# pot-boardD.net
KiCad netlist of a schematic drawn in EAGLE
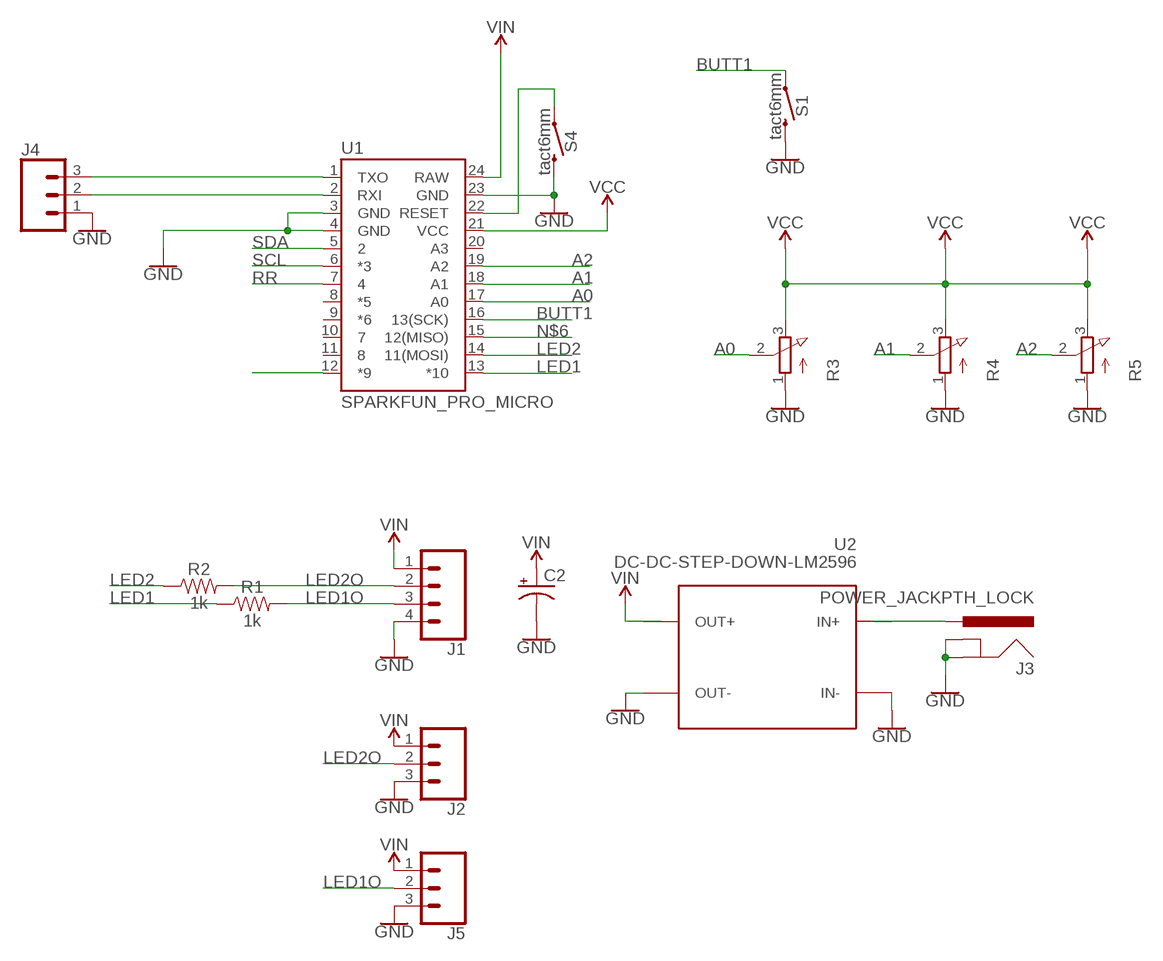
[diagram p0: schematic, sheet 1]

(export (version "E")
  (design (tool "Eeschema 10.0.6"))
  (components
    (comp (ref "C2")
      (value "CPOL-USE3.5-8")
      (footprint "eagle-import:E3,5-8")
      (libsource (lib "eagle-import") (part "CPOL-USE3.5-8"))
    )
    (comp (ref "J1")
      (value "CONN_04")
      (footprint "eagle-import:1X04")
      (libsource (lib "eagle-import") (part "CONN_04"))
    )
    (comp (ref "J2")
      (value "CONN_03")
      (footprint "eagle-import:1X03")
      (libsource (lib "eagle-import") (part "CONN_03"))
    )
    (comp (ref "J3")
      (value "POWER_JACKPTH_LOCK")
      (footprint "eagle-import:POWER_JACK_PTH_LOCK")
      (libsource (lib "eagle-import") (part "POWER_JACKPTH_LOCK"))
    )
    (comp (ref "J4")
      (value "CONN_03")
      (footprint "eagle-import:1X03")
      (libsource (lib "eagle-import") (part "CONN_03"))
    )
    (comp (ref "J5")
      (value "CONN_03")
      (footprint "eagle-import:1X03")
      (libsource (lib "eagle-import") (part "CONN_03"))
    )
    (comp (ref "R1")
      (value "1k")
      (footprint "eagle-import:AXIAL-0.3")
      (libsource (lib "eagle-import") (part "1KOHM-HORIZ-1/4W-5%"))
    )
    (comp (ref "R2")
      (value "1k")
      (footprint "eagle-import:AXIAL-0.3")
      (libsource (lib "eagle-import") (part "1KOHM-HORIZ-1/4W-5%"))
    )
    (comp (ref "R3")
      (value "3RP/1610N")
      (footprint "eagle-import:3RP_1610N")
      (libsource (lib "eagle-import") (part "3RP/1610N"))
    )
    (comp (ref "R4")
      (value "3RP/1610N")
      (footprint "eagle-import:3RP_1610N")
      (libsource (lib "eagle-import") (part "3RP/1610N"))
    )
    (comp (ref "R5")
      (value "3RP/1610N")
      (footprint "eagle-import:3RP_1610N")
      (libsource (lib "eagle-import") (part "3RP/1610N"))
    )
    (comp (ref "S1")
      (value "tact6mm")
      (footprint "eagle-import:TACTILE_SWITCH_PTH_6.0MM")
      (libsource (lib "eagle-import") (part "MOMENTARY-SWITCH-SPST-PTH-6.0MM"))
    )
    (comp (ref "S4")
      (value "tact6mm")
      (footprint "eagle-import:TACTILE_SWITCH_PTH_6.0MM")
      (libsource (lib "eagle-import") (part "MOMENTARY-SWITCH-SPST-PTH-6.0MM"))
    )
    (comp (ref "U1")
      (value "SPARKFUN_PRO_MICRO")
      (footprint "eagle-import:SPARKFUN_PRO_MICRO")
      (libsource (lib "eagle-import") (part "SPARKFUN_PRO_MICRO"))
    )
    (comp (ref "U2")
      (value "DC-DC-STEP-DOWN-LM2596")
      (footprint "eagle-import:DC-DC-STEP-DOWN-LM2596")
      (libsource (lib "eagle-import") (part "DC-DC-STEP-DOWN-LM2596"))
    )
  )
  (nets
    (net (code "1") (name "/A0") (class "Default")
      (node (ref "R3") (pin "2") (pinfunction "S_2") (pintype "passive"))
      (node (ref "U1") (pin "17") (pinfunction "A0_17") (pintype "bidirectional"))
    )
    (net (code "2") (name "/A1") (class "Default")
      (node (ref "R4") (pin "2") (pinfunction "S_2") (pintype "passive"))
      (node (ref "U1") (pin "18") (pinfunction "A1_18") (pintype "bidirectional"))
    )
    (net (code "3") (name "/A2") (class "Default")
      (node (ref "R5") (pin "2") (pinfunction "S_2") (pintype "passive"))
      (node (ref "U1") (pin "19") (pinfunction "A2_19") (pintype "bidirectional"))
    )
    (net (code "4") (name "/BUTT1") (class "Default")
      (node (ref "S1") (pin "1") (pinfunction "1_1") (pintype "passive"))
      (node (ref "U1") (pin "16") (pinfunction "13(SCK)_16") (pintype "bidirectional"))
    )
    (net (code "5") (name "/LED1") (class "Default")
      (node (ref "R1") (pin "P$1") (pinfunction "1_P$1") (pintype "passive"))
      (node (ref "U1") (pin "13") (pinfunction "*10_13") (pintype "bidirectional"))
    )
    (net (code "6") (name "/LED1O") (class "Default")
      (node (ref "J1") (pin "3") (pinfunction "3_3") (pintype "passive"))
      (node (ref "J5") (pin "2") (pinfunction "2_2") (pintype "passive"))
      (node (ref "R1") (pin "P$2") (pinfunction "2_P$2") (pintype "passive"))
    )
    (net (code "7") (name "/LED2") (class "Default")
      (node (ref "R2") (pin "P$1") (pinfunction "1_P$1") (pintype "passive"))
      (node (ref "U1") (pin "14") (pinfunction "11(MOSI)_14") (pintype "bidirectional"))
    )
    (net (code "8") (name "/LED2O") (class "Default")
      (node (ref "J1") (pin "2") (pinfunction "2_2") (pintype "passive"))
      (node (ref "J2") (pin "2") (pinfunction "2_2") (pintype "passive"))
      (node (ref "R2") (pin "P$2") (pinfunction "2_P$2") (pintype "passive"))
    )
    (net (code "9") (name "/N$6") (class "Default")
      (node (ref "U1") (pin "15") (pinfunction "12(MISO)_15") (pintype "bidirectional"))
    )
    (net (code "10") (name "/RR") (class "Default")
      (node (ref "U1") (pin "7") (pinfunction "4_7") (pintype "bidirectional"))
    )
    (net (code "11") (name "/SCL") (class "Default")
      (node (ref "U1") (pin "6") (pinfunction "*3_6") (pintype "bidirectional"))
    )
    (net (code "12") (name "/SDA") (class "Default")
      (node (ref "U1") (pin "5") (pinfunction "2_5") (pintype "bidirectional"))
    )
    (net (code "13") (name "GND") (class "Default")
      (node (ref "C2") (pin "-") (pinfunction "-_-") (pintype "passive"))
      (node (ref "J1") (pin "4") (pinfunction "4_4") (pintype "passive"))
      (node (ref "J2") (pin "3") (pinfunction "3_3") (pintype "passive"))
      (node (ref "J3") (pin "GND") (pinfunction "GND_GND") (pintype "bidirectional"))
      (node (ref "J3") (pin "GNDBREAK") (pinfunction "GNDBREAK_GNDBREAK") (pintype "bidirectional"))
      (node (ref "J4") (pin "1") (pinfunction "1_1") (pintype "passive"))
      (node (ref "J5") (pin "3") (pinfunction "3_3") (pintype "passive"))
      (node (ref "R3") (pin "1") (pinfunction "A_1") (pintype "passive"))
      (node (ref "R4") (pin "1") (pinfunction "A_1") (pintype "passive"))
      (node (ref "R5") (pin "1") (pinfunction "A_1") (pintype "passive"))
      (node (ref "S1") (pin "3") (pinfunction "2_3") (pintype "passive"))
      (node (ref "S4") (pin "3") (pinfunction "2_3") (pintype "passive"))
      (node (ref "U1") (pin "23") (pinfunction "GND_23") (pintype "power_in"))
      (node (ref "U1") (pin "3") (pinfunction "GND_3") (pintype "power_in"))
      (node (ref "U1") (pin "4") (pinfunction "GND_4") (pintype "power_in"))
      (node (ref "U2") (pin "IN-") (pinfunction "IN-_IN-") (pintype "bidirectional"))
      (node (ref "U2") (pin "OUT-") (pinfunction "OUT-_OUT-") (pintype "bidirectional"))
    )
    (net (code "14") (name "Net-(J3-PadPWR)") (class "Default")
      (node (ref "J3") (pin "PWR") (pinfunction "PWR_PWR") (pintype "bidirectional"))
      (node (ref "U2") (pin "IN+") (pinfunction "IN+_IN+") (pintype "bidirectional"))
    )
    (net (code "15") (name "Net-(U1-RESET)") (class "Default")
      (node (ref "S4") (pin "1") (pinfunction "1_1") (pintype "passive"))
      (node (ref "U1") (pin "22") (pinfunction "RESET_22") (pintype "bidirectional"))
    )
    (net (code "16") (name "Net-(U1-RXI)") (class "Default")
      (node (ref "J4") (pin "2") (pinfunction "2_2") (pintype "passive"))
      (node (ref "U1") (pin "2") (pinfunction "RXI_2") (pintype "bidirectional"))
    )
    (net (code "17") (name "Net-(U1-TXO)") (class "Default")
      (node (ref "J4") (pin "3") (pinfunction "3_3") (pintype "passive"))
      (node (ref "U1") (pin "1") (pinfunction "TXO_1") (pintype "bidirectional"))
    )
    (net (code "18") (name "VCC") (class "Default")
      (node (ref "R3") (pin "3") (pinfunction "E_3") (pintype "passive"))
      (node (ref "R4") (pin "3") (pinfunction "E_3") (pintype "passive"))
      (node (ref "R5") (pin "3") (pinfunction "E_3") (pintype "passive"))
      (node (ref "U1") (pin "21") (pinfunction "VCC_21") (pintype "power_in"))
    )
    (net (code "19") (name "VIN") (class "Default")
      (node (ref "C2") (pin "+") (pinfunction "+_+") (pintype "passive"))
      (node (ref "J1") (pin "1") (pinfunction "1_1") (pintype "passive"))
      (node (ref "J2") (pin "1") (pinfunction "1_1") (pintype "passive"))
      (node (ref "J5") (pin "1") (pinfunction "1_1") (pintype "passive"))
      (node (ref "U1") (pin "24") (pinfunction "RAW_24") (pintype "power_in"))
    )
    (net (code "20") (name "unconnected-(U1-*5-Pad8)") (class "Default")
      (node (ref "U1") (pin "8") (pinfunction "*5_8") (pintype "bidirectional"))
    )
    (net (code "21") (name "unconnected-(U1-*6-Pad9)") (class "Default")
      (node (ref "U1") (pin "9") (pinfunction "*6_9") (pintype "bidirectional"))
    )
    (net (code "22") (name "unconnected-(U1-*9-Pad12)") (class "Default")
      (node (ref "U1") (pin "12") (pinfunction "*9_12") (pintype "bidirectional"))
    )
    (net (code "23") (name "unconnected-(U1-7-Pad10)") (class "Default")
      (node (ref "U1") (pin "10") (pinfunction "7_10") (pintype "bidirectional"))
    )
    (net (code "24") (name "unconnected-(U1-8-Pad11)") (class "Default")
      (node (ref "U1") (pin "11") (pinfunction "8_11") (pintype "bidirectional"))
    )
    (net (code "25") (name "unconnected-(U1-A3-Pad20)") (class "Default")
      (node (ref "U1") (pin "20") (pinfunction "A3_20") (pintype "bidirectional"))
    )
    (net (code "26") (name "unconnected-(U2-PadOUT+)") (class "Default")
      (node (ref "U2") (pin "OUT+") (pinfunction "OUT+_OUT+") (pintype "bidirectional"))
    )
  )
)
